# MCU.net
KiCad netlist of a schematic drawn in Altium Designer
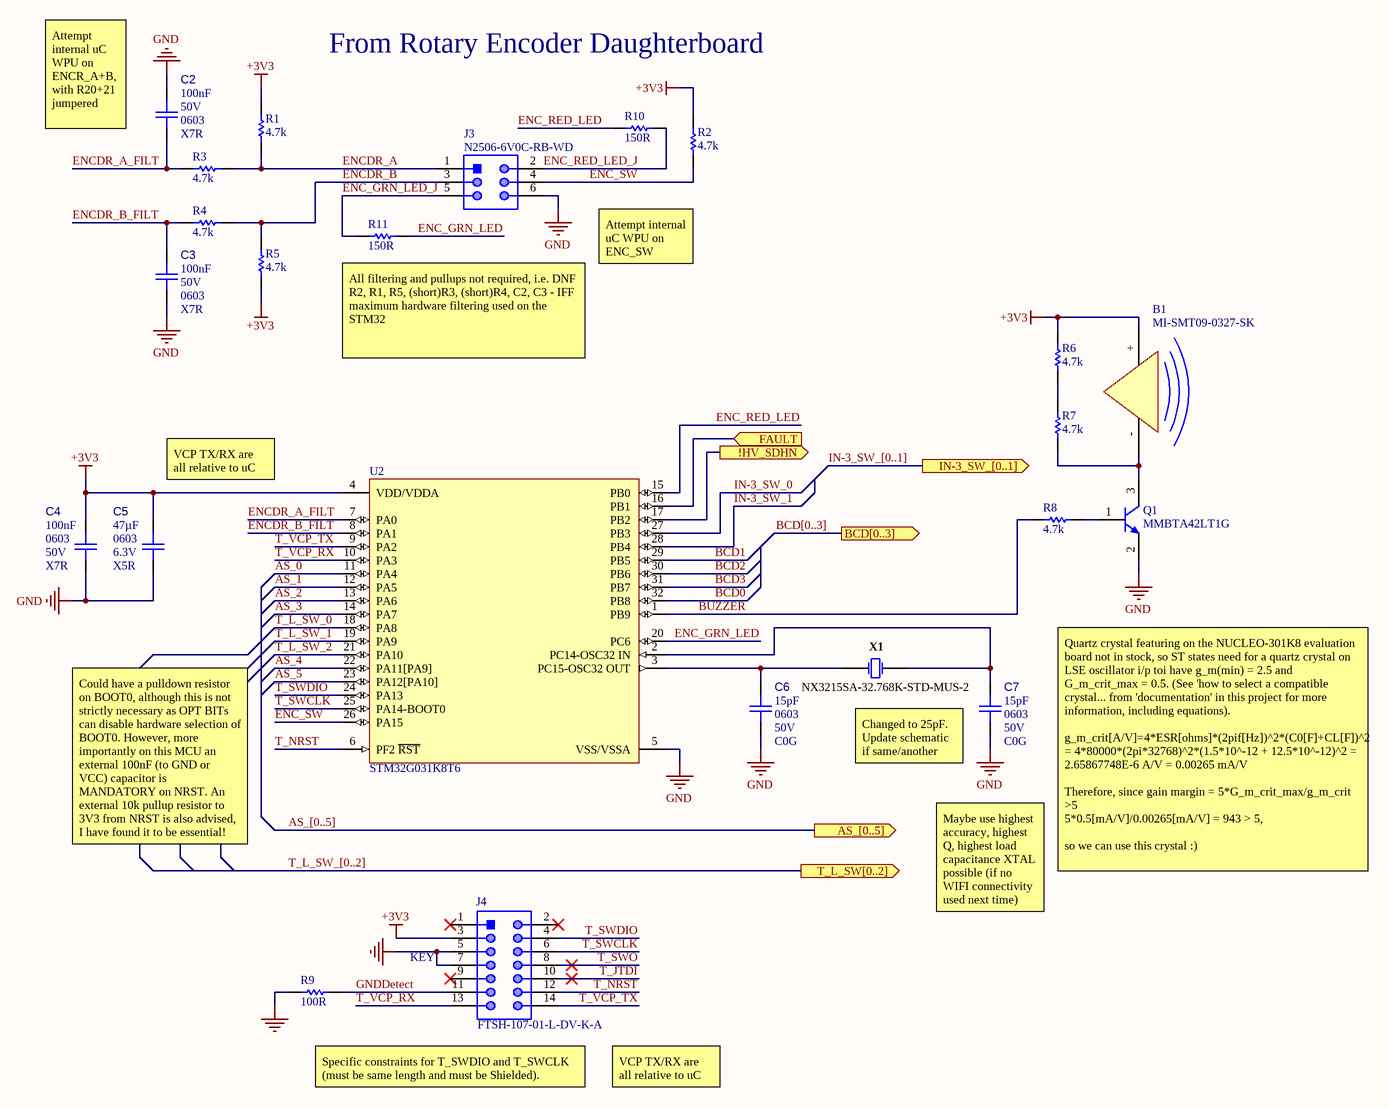
[diagram p0: MCU.SchDoc]

(export (version "E")
  (design (tool "Eeschema 10.0.6"))
  (components
    (comp (ref "B1")
      (value "MI-SMT09-0327-SK")
      (footprint "INDP9696X53N")
      (description "Magnetic Indicator SMT 9.6MM 3V")
      (libsource (lib "KETS Quantum Security") (part "MI-SMT09-0327-SK-Symbol-1"))
    )
    (comp (ref "C2")
      (value "100nF")
      (footprint "CAPC1608X09N")
      (fields
        (field (name "VOLTAGE RATING") "50V")
        (field (name "TOLERANCE") "10%")
        (field (name "CASE/PACKAGE") "0603")
        (field (name "DIELECTRIC") "X7R")
        (field (name "Comment") "CGA3E2X7R1H104K080AA")
      )
      (libsource (lib "KETS Quantum Security") (part "CAP-NP-2"))
    )
    (comp (ref "C3")
      (value "100nF")
      (footprint "CAPC1608X09N")
      (fields
        (field (name "VOLTAGE RATING") "50V")
        (field (name "TOLERANCE") "10%")
        (field (name "CASE/PACKAGE") "0603")
        (field (name "DIELECTRIC") "X7R")
        (field (name "Comment") "CGA3E2X7R1H104K080AA")
      )
      (libsource (lib "KETS Quantum Security") (part "CAP-NP-2"))
    )
    (comp (ref "C4")
      (value "100nF")
      (footprint "CAPC1608X09N")
      (fields
        (field (name "VOLTAGE RATING") "50V")
        (field (name "TOLERANCE") "10%")
        (field (name "CASE/PACKAGE") "0603")
        (field (name "DIELECTRIC") "X7R")
        (field (name "Comment") "CGA3E2X7R1H104K080AA")
      )
      (libsource (lib "KETS Quantum Security") (part "CAP-NP-2"))
    )
    (comp (ref "C5")
      (value "47µF")
      (footprint "CAPC1608X87X35NL15T15")
      (description "0603 (1608Metric) CERAMIC CAPACITOR ceramic capacitor 6.3V 47uF ±20% X5R")
      (fields
        (field (name "TOLERANCE") "20%")
        (field (name "DIELECTRIC") "X5R")
        (field (name "VOLTAGE RATING") "6.3V")
        (field (name "CASE/PACKAGE") "0603")
        (field (name "Comment") "06036D476MAT2A")
      )
      (libsource (lib "KETS Quantum Security") (part "CAP-NP-2"))
    )
    (comp (ref "C6")
      (value "15pF")
      (footprint "CAPC1608X87X35NL15T15")
      (description "Cap Ceramic 15pF 50V C0G 5% Pad SMD 0603 Flexible Termination 125C Extreme Low ESR T/R")
      (fields
        (field (name "VOLTAGE RATING") "50V")
        (field (name "TOLERANCE") "5%")
        (field (name "DIELECTRIC") "C0G")
        (field (name "CASE/PACKAGE") "0603")
        (field (name "Comment") "C0603X150J5GACTU")
      )
      (libsource (lib "KETS Quantum Security") (part "CAP-NP-2"))
    )
    (comp (ref "C7")
      (value "15pF")
      (footprint "CAPC1608X87X35NL15T15")
      (description "Cap Ceramic 15pF 50V C0G 5% Pad SMD 0603 Flexible Termination 125C Extreme Low ESR T/R")
      (fields
        (field (name "VOLTAGE RATING") "50V")
        (field (name "TOLERANCE") "5%")
        (field (name "DIELECTRIC") "C0G")
        (field (name "CASE/PACKAGE") "0603")
        (field (name "Comment") "C0603X150J5GACTU")
      )
      (libsource (lib "KETS Quantum Security") (part "CAP-NP-2"))
    )
    (comp (ref "J3")
      (value "N2506-6V0C-RB-WD")
      (footprint "N2506-6V0C-RB-WD-Footprint-1")
      (description "80001386988 N2506-6V0C-Rb-Wd=06//Ht/Vsmt/30U/Rohs/Cap/T&r")
      (libsource (lib "KETS Quantum Security") (part "N2506-6V0C-RB-WD-Symbol-1"))
    )
    (comp (ref "J4")
      (value "FTSH-107-01-L-DV-K-A")
      (footprint "FP-FTSH-107-01-L-DV-K-A-MFG")
      (description "Conn Unshrouded Header HDR 14 POS 1.27mm Solder ST Top Entry SMD TIGER CLAW™ Tube")
      (libsource (lib "KETS Quantum Security") (part "FTSH-107-01-L-DV-K-A-Symbol-1"))
    )
    (comp (ref "Q1")
      (value "MMBTA42LT1G")
      (footprint "ONSC-SOT-23-3-318-08_V")
      (libsource (lib "KETS Quantum Security") (part "ONSC-NPN-B1E2C3-3"))
    )
    (comp (ref "R1")
      (value "4.7k")
      (footprint "RESC1608X55X25NL10T15")
      (description "Chip Resistor, 4.7 KOhm, +/- 1%, 0.1 W, -55 to 155 degC, 0603 (1608 Metric)")
      (fields (field (name "TOLERANCE") "1%") (field (name "POWER") "100mW"))
      (libsource (lib "KETS Quantum Security") (part "RES-2"))
    )
    (comp (ref "R2")
      (value "4.7k")
      (footprint "RESC1608X55X25NL10T15")
      (description "Chip Resistor, 4.7 KOhm, +/- 1%, 0.1 W, -55 to 155 degC, 0603 (1608 Metric)")
      (fields (field (name "TOLERANCE") "1%") (field (name "POWER") "100mW"))
      (libsource (lib "KETS Quantum Security") (part "RES-2"))
    )
    (comp (ref "R3")
      (value "4.7k")
      (footprint "RESC1608X55X25NL10T15")
      (description "Chip Resistor, 4.7 KOhm, +/- 1%, 0.1 W, -55 to 155 degC, 0603 (1608 Metric)")
      (fields (field (name "TOLERANCE") "1%") (field (name "POWER") "100mW"))
      (libsource (lib "KETS Quantum Security") (part "RES-2"))
    )
    (comp (ref "R4")
      (value "4.7k")
      (footprint "RESC1608X55X25NL10T15")
      (description "Chip Resistor, 4.7 KOhm, +/- 1%, 0.1 W, -55 to 155 degC, 0603 (1608 Metric)")
      (fields (field (name "TOLERANCE") "1%") (field (name "POWER") "100mW"))
      (libsource (lib "KETS Quantum Security") (part "RES-2"))
    )
    (comp (ref "R5")
      (value "4.7k")
      (footprint "RESC1608X55X25NL10T15")
      (description "Chip Resistor, 4.7 KOhm, +/- 1%, 0.1 W, -55 to 155 degC, 0603 (1608 Metric)")
      (fields (field (name "TOLERANCE") "1%") (field (name "POWER") "100mW"))
      (libsource (lib "KETS Quantum Security") (part "RES-2"))
    )
    (comp (ref "R6")
      (value "4.7k")
      (footprint "RESC1608X55X25NL10T15")
      (description "Chip Resistor, 4.7 KOhm, +/- 1%, 0.1 W, -55 to 155 degC, 0603 (1608 Metric)")
      (fields (field (name "TOLERANCE") "1%") (field (name "POWER") "100mW"))
      (libsource (lib "KETS Quantum Security") (part "RES-2"))
    )
    (comp (ref "R7")
      (value "4.7k")
      (footprint "RESC1608X55X25NL10T15")
      (description "Chip Resistor, 4.7 KOhm, +/- 1%, 0.1 W, -55 to 155 degC, 0603 (1608 Metric)")
      (fields (field (name "TOLERANCE") "1%") (field (name "POWER") "100mW"))
      (libsource (lib "KETS Quantum Security") (part "RES-2"))
    )
    (comp (ref "R8")
      (value "4.7k")
      (footprint "RESC1608X55X25NL10T15")
      (description "Chip Resistor, 4.7 KOhm, +/- 1%, 0.1 W, -55 to 155 degC, 0603 (1608 Metric)")
      (fields (field (name "TOLERANCE") "1%") (field (name "POWER") "100mW"))
      (libsource (lib "KETS Quantum Security") (part "RES-2"))
    )
    (comp (ref "R9")
      (value "100R")
      (footprint "RESC1608X55X25NL10T15")
      (fields
        (field (name "POWER") "100mW")
        (field (name "TOLERANCE") "1%")
        (field (name "Comment") "ERJ-3EKF1000V")
      )
      (libsource (lib "KETS Quantum Security") (part "RES-2"))
    )
    (comp (ref "R10")
      (value "150R")
      (footprint "RESC1608X55X25NL10T15")
      (description "Res Thick Film 0603 150 Ohm 1% 1/3W ±100ppm/°C Molded SMD SMD Paper T/R")
      (fields (field (name "TOLERANCE") "1%") (field (name "POWER") "100mW"))
      (libsource (lib "KETS Quantum Security") (part "RES-2"))
    )
    (comp (ref "R11")
      (value "150R")
      (footprint "RESC1608X55X25NL10T15")
      (description "Res Thick Film 0603 150 Ohm 1% 1/3W ±100ppm/°C Molded SMD SMD Paper T/R")
      (fields (field (name "TOLERANCE") "1%") (field (name "POWER") "100mW"))
      (libsource (lib "KETS Quantum Security") (part "RES-2"))
    )
    (comp (ref "U2")
      (value "STM32G031K8T6")
      (footprint "TQFP80P900X900X160-32N")
      (description "RISC Microcontroller, 32-Bit, FLASH, CORTEX-M0 CPU, 64MHz, CMOS, PQFP32")
      (libsource (lib "KETS Quantum Security") (part "473aa7f4ee034338f9424f96f5febff"))
    )
    (comp (ref "X1")
      (value "NX3215SA-32.768K-STD-MUS-2")
      (footprint "NX3215SA-32.768K-STD-MUS-2-Footprint-1")
      (description "Crystal 0.032768MHz ±20ppm (Tol) 12.5pF FUND 80000Ohm Automotive AEC-Q200 2-Pin SMD")
      (fields (field (name "TOLERANCE") "0.002%"))
      (libsource (lib "KETS Quantum Security") (part "XTAL-2"))
    )
  )
  (nets
    (net (code "1") (name "+3V3") (class "Default")
      (node (ref "B1") (pin "+") (pinfunction "VCC_+") (pintype "passive"))
      (node (ref "C4") (pin "1") (pinfunction "1_1") (pintype "passive"))
      (node (ref "C5") (pin "1") (pinfunction "1_1") (pintype "passive"))
      (node (ref "J4") (pin "3") (pinfunction "3_3") (pintype "passive"))
      (node (ref "R1") (pin "2") (pinfunction "2_2") (pintype "passive"))
      (node (ref "R2") (pin "2") (pinfunction "2_2") (pintype "passive"))
      (node (ref "R5") (pin "1") (pinfunction "1_1") (pintype "passive"))
      (node (ref "R6") (pin "2") (pinfunction "2_2") (pintype "passive"))
      (node (ref "U2") (pin "4") (pinfunction "VDD/VDDA_4") (pintype "power_in"))
    )
    (net (code "2") (name "/!HV_SDHN") (class "Default")
      (node (ref "U2") (pin "17") (pinfunction "PB2_17") (pintype "bidirectional"))
    )
    (net (code "3") (name "/AS_0") (class "Default")
      (node (ref "U2") (pin "11") (pinfunction "PA4_11") (pintype "bidirectional"))
    )
    (net (code "4") (name "/AS_1") (class "Default")
      (node (ref "U2") (pin "12") (pinfunction "PA5_12") (pintype "bidirectional"))
    )
    (net (code "5") (name "/AS_2") (class "Default")
      (node (ref "U2") (pin "13") (pinfunction "PA6_13") (pintype "bidirectional"))
    )
    (net (code "6") (name "/AS_3") (class "Default")
      (node (ref "U2") (pin "14") (pinfunction "PA7_14") (pintype "bidirectional"))
    )
    (net (code "7") (name "/AS_4") (class "Default")
      (node (ref "U2") (pin "22") (pinfunction "PA11[PA9]_22") (pintype "bidirectional"))
    )
    (net (code "8") (name "/AS_5") (class "Default")
      (node (ref "U2") (pin "23") (pinfunction "PA12[PA10]_23") (pintype "bidirectional"))
    )
    (net (code "10") (name "/BCD0") (class "Default")
      (node (ref "U2") (pin "32") (pinfunction "PB8_32") (pintype "bidirectional"))
    )
    (net (code "11") (name "/BCD1") (class "Default")
      (node (ref "U2") (pin "29") (pinfunction "PB5_29") (pintype "bidirectional"))
    )
    (net (code "12") (name "/BCD2") (class "Default")
      (node (ref "U2") (pin "30") (pinfunction "PB6_30") (pintype "bidirectional"))
    )
    (net (code "13") (name "/BCD3") (class "Default")
      (node (ref "U2") (pin "31") (pinfunction "PB7_31") (pintype "bidirectional"))
    )
    (net (code "15") (name "/BUZZER") (class "Default")
      (node (ref "R8") (pin "1") (pinfunction "1_1") (pintype "passive"))
      (node (ref "U2") (pin "1") (pinfunction "PB9_1") (pintype "bidirectional"))
    )
    (net (code "16") (name "/ENCDR_A") (class "Default")
      (node (ref "J3") (pin "1") (pinfunction "1_1") (pintype "passive"))
      (node (ref "R1") (pin "1") (pinfunction "1_1") (pintype "passive"))
      (node (ref "R3") (pin "2") (pinfunction "2_2") (pintype "passive"))
    )
    (net (code "17") (name "/ENCDR_A_FILT") (class "Default")
      (node (ref "C2") (pin "1") (pinfunction "1_1") (pintype "passive"))
      (node (ref "R3") (pin "1") (pinfunction "1_1") (pintype "passive"))
      (node (ref "U2") (pin "7") (pinfunction "PA0_7") (pintype "bidirectional"))
    )
    (net (code "18") (name "/ENCDR_B") (class "Default")
      (node (ref "J3") (pin "3") (pinfunction "3_3") (pintype "passive"))
      (node (ref "R4") (pin "2") (pinfunction "2_2") (pintype "passive"))
      (node (ref "R5") (pin "2") (pinfunction "2_2") (pintype "passive"))
    )
    (net (code "19") (name "/ENCDR_B_FILT") (class "Default")
      (node (ref "C3") (pin "2") (pinfunction "2_2") (pintype "passive"))
      (node (ref "R4") (pin "1") (pinfunction "1_1") (pintype "passive"))
      (node (ref "U2") (pin "8") (pinfunction "PA1_8") (pintype "bidirectional"))
    )
    (net (code "20") (name "/ENC_GRN_LED") (class "Default")
      (node (ref "R11") (pin "2") (pinfunction "2_2") (pintype "passive"))
      (node (ref "U2") (pin "20") (pinfunction "PC6_20") (pintype "bidirectional"))
    )
    (net (code "21") (name "/ENC_GRN_LED_J") (class "Default")
      (node (ref "J3") (pin "5") (pinfunction "5_5") (pintype "passive"))
      (node (ref "R11") (pin "1") (pinfunction "1_1") (pintype "passive"))
    )
    (net (code "22") (name "/ENC_RED_LED") (class "Default")
      (node (ref "R10") (pin "2") (pinfunction "2_2") (pintype "passive"))
      (node (ref "U2") (pin "15") (pinfunction "PB0_15") (pintype "bidirectional"))
    )
    (net (code "23") (name "/ENC_RED_LED_J") (class "Default")
      (node (ref "J3") (pin "2") (pinfunction "2_2") (pintype "passive"))
      (node (ref "R10") (pin "1") (pinfunction "1_1") (pintype "passive"))
    )
    (net (code "24") (name "/ENC_SW") (class "Default")
      (node (ref "J3") (pin "4") (pinfunction "4_4") (pintype "passive"))
      (node (ref "R2") (pin "1") (pinfunction "1_1") (pintype "passive"))
      (node (ref "U2") (pin "26") (pinfunction "PA15_26") (pintype "bidirectional"))
    )
    (net (code "25") (name "/FAULT") (class "Default")
      (node (ref "U2") (pin "16") (pinfunction "PB1_16") (pintype "bidirectional"))
    )
    (net (code "26") (name "/GNDDetect") (class "Default")
      (node (ref "J4") (pin "11") (pinfunction "11_11") (pintype "passive"))
      (node (ref "R9") (pin "2") (pinfunction "2_2") (pintype "passive"))
    )
    (net (code "27") (name "/IN-3_SW_0") (class "Default")
      (node (ref "U2") (pin "27") (pinfunction "PB3_27") (pintype "bidirectional"))
    )
    (net (code "28") (name "/IN-3_SW_1") (class "Default")
      (node (ref "U2") (pin "28") (pinfunction "PB4_28") (pintype "bidirectional"))
    )
    (net (code "30") (name "/T_JTDI") (class "Default")
      (node (ref "J4") (pin "10") (pinfunction "10_10") (pintype "passive"))
    )
    (net (code "31") (name "/T_L_SW_0") (class "Default")
      (node (ref "U2") (pin "18") (pinfunction "PA8_18") (pintype "bidirectional"))
    )
    (net (code "32") (name "/T_L_SW_1") (class "Default")
      (node (ref "U2") (pin "19") (pinfunction "PA9_19") (pintype "bidirectional"))
    )
    (net (code "33") (name "/T_L_SW_2") (class "Default")
      (node (ref "U2") (pin "21") (pinfunction "PA10_21") (pintype "bidirectional"))
    )
    (net (code "35") (name "/T_NRST") (class "Default")
      (node (ref "J4") (pin "12") (pinfunction "12_12") (pintype "passive"))
      (node (ref "U2") (pin "6") (pinfunction "PF2_~{RST}_6") (pintype "input"))
    )
    (net (code "36") (name "/T_SWCLK") (class "Default")
      (node (ref "J4") (pin "6") (pinfunction "6_6") (pintype "passive"))
      (node (ref "U2") (pin "25") (pinfunction "PA14-BOOT0_25") (pintype "bidirectional"))
    )
    (net (code "37") (name "/T_SWDIO") (class "Default")
      (node (ref "J4") (pin "4") (pinfunction "4_4") (pintype "passive"))
      (node (ref "U2") (pin "24") (pinfunction "PA13_24") (pintype "bidirectional"))
    )
    (net (code "38") (name "/T_SWO") (class "Default")
      (node (ref "J4") (pin "8") (pinfunction "8_8") (pintype "passive"))
    )
    (net (code "39") (name "/T_VCP_RX") (class "Default")
      (node (ref "J4") (pin "13") (pinfunction "13_13") (pintype "passive"))
      (node (ref "U2") (pin "10") (pinfunction "PA3_10") (pintype "bidirectional"))
    )
    (net (code "40") (name "/T_VCP_TX") (class "Default")
      (node (ref "J4") (pin "14") (pinfunction "14_14") (pintype "passive"))
      (node (ref "U2") (pin "9") (pinfunction "PA2_9") (pintype "bidirectional"))
    )
    (net (code "41") (name "GND") (class "Default")
      (node (ref "C2") (pin "2") (pinfunction "2_2") (pintype "passive"))
      (node (ref "C3") (pin "1") (pinfunction "1_1") (pintype "passive"))
      (node (ref "C4") (pin "2") (pinfunction "2_2") (pintype "passive"))
      (node (ref "C5") (pin "2") (pinfunction "2_2") (pintype "passive"))
      (node (ref "C6") (pin "2") (pinfunction "2_2") (pintype "passive"))
      (node (ref "C7") (pin "2") (pinfunction "2_2") (pintype "passive"))
      (node (ref "J3") (pin "6") (pinfunction "6_6") (pintype "passive"))
      (node (ref "J4") (pin "5") (pinfunction "5_5") (pintype "passive"))
      (node (ref "J4") (pin "7") (pinfunction "7_7") (pintype "passive"))
      (node (ref "Q1") (pin "2") (pinfunction "E_2") (pintype "passive"))
      (node (ref "R9") (pin "1") (pinfunction "1_1") (pintype "passive"))
      (node (ref "U2") (pin "5") (pinfunction "VSS/VSSA_5") (pintype "power_in"))
    )
    (net (code "42") (name "Net-(B1-GND)") (class "Default")
      (node (ref "B1") (pin "-") (pinfunction "GND_-") (pintype "passive"))
      (node (ref "Q1") (pin "3") (pinfunction "C_3") (pintype "passive"))
      (node (ref "R7") (pin "1") (pinfunction "1_1") (pintype "passive"))
    )
    (net (code "43") (name "Net-(Q1-B)") (class "Default")
      (node (ref "Q1") (pin "1") (pinfunction "B_1") (pintype "passive"))
      (node (ref "R8") (pin "2") (pinfunction "2_2") (pintype "passive"))
    )
    (net (code "44") (name "Net-(R6-Pad1)") (class "Default")
      (node (ref "R6") (pin "1") (pinfunction "1_1") (pintype "passive"))
      (node (ref "R7") (pin "2") (pinfunction "2_2") (pintype "passive"))
    )
    (net (code "45") (name "Net-(U2-PC14-OSC32_IN)") (class "Default")
      (node (ref "C7") (pin "1") (pinfunction "1_1") (pintype "passive"))
      (node (ref "U2") (pin "2") (pinfunction "PC14-OSC32_IN_2") (pintype "input"))
      (node (ref "X1") (pin "2") (pinfunction "2_2") (pintype "passive"))
    )
    (net (code "46") (name "Net-(U2-PC15-OSC32_OUT)") (class "Default")
      (node (ref "C6") (pin "1") (pinfunction "1_1") (pintype "passive"))
      (node (ref "U2") (pin "3") (pinfunction "PC15-OSC32_OUT_3") (pintype "output"))
      (node (ref "X1") (pin "1") (pinfunction "1_1") (pintype "passive"))
    )
    (net (code "47") (name "unconnected-(J4-Pad1)") (class "Default")
      (node (ref "J4") (pin "1") (pinfunction "1_1") (pintype "passive+no_connect"))
    )
    (net (code "48") (name "unconnected-(J4-Pad2)") (class "Default")
      (node (ref "J4") (pin "2") (pinfunction "2_2") (pintype "passive+no_connect"))
    )
    (net (code "49") (name "unconnected-(J4-Pad9)") (class "Default")
      (node (ref "J4") (pin "9") (pinfunction "9_9") (pintype "passive+no_connect"))
    )
  )
)
